# AMP_BB.net
KiCad netlist of a schematic drawn in Altium Designer
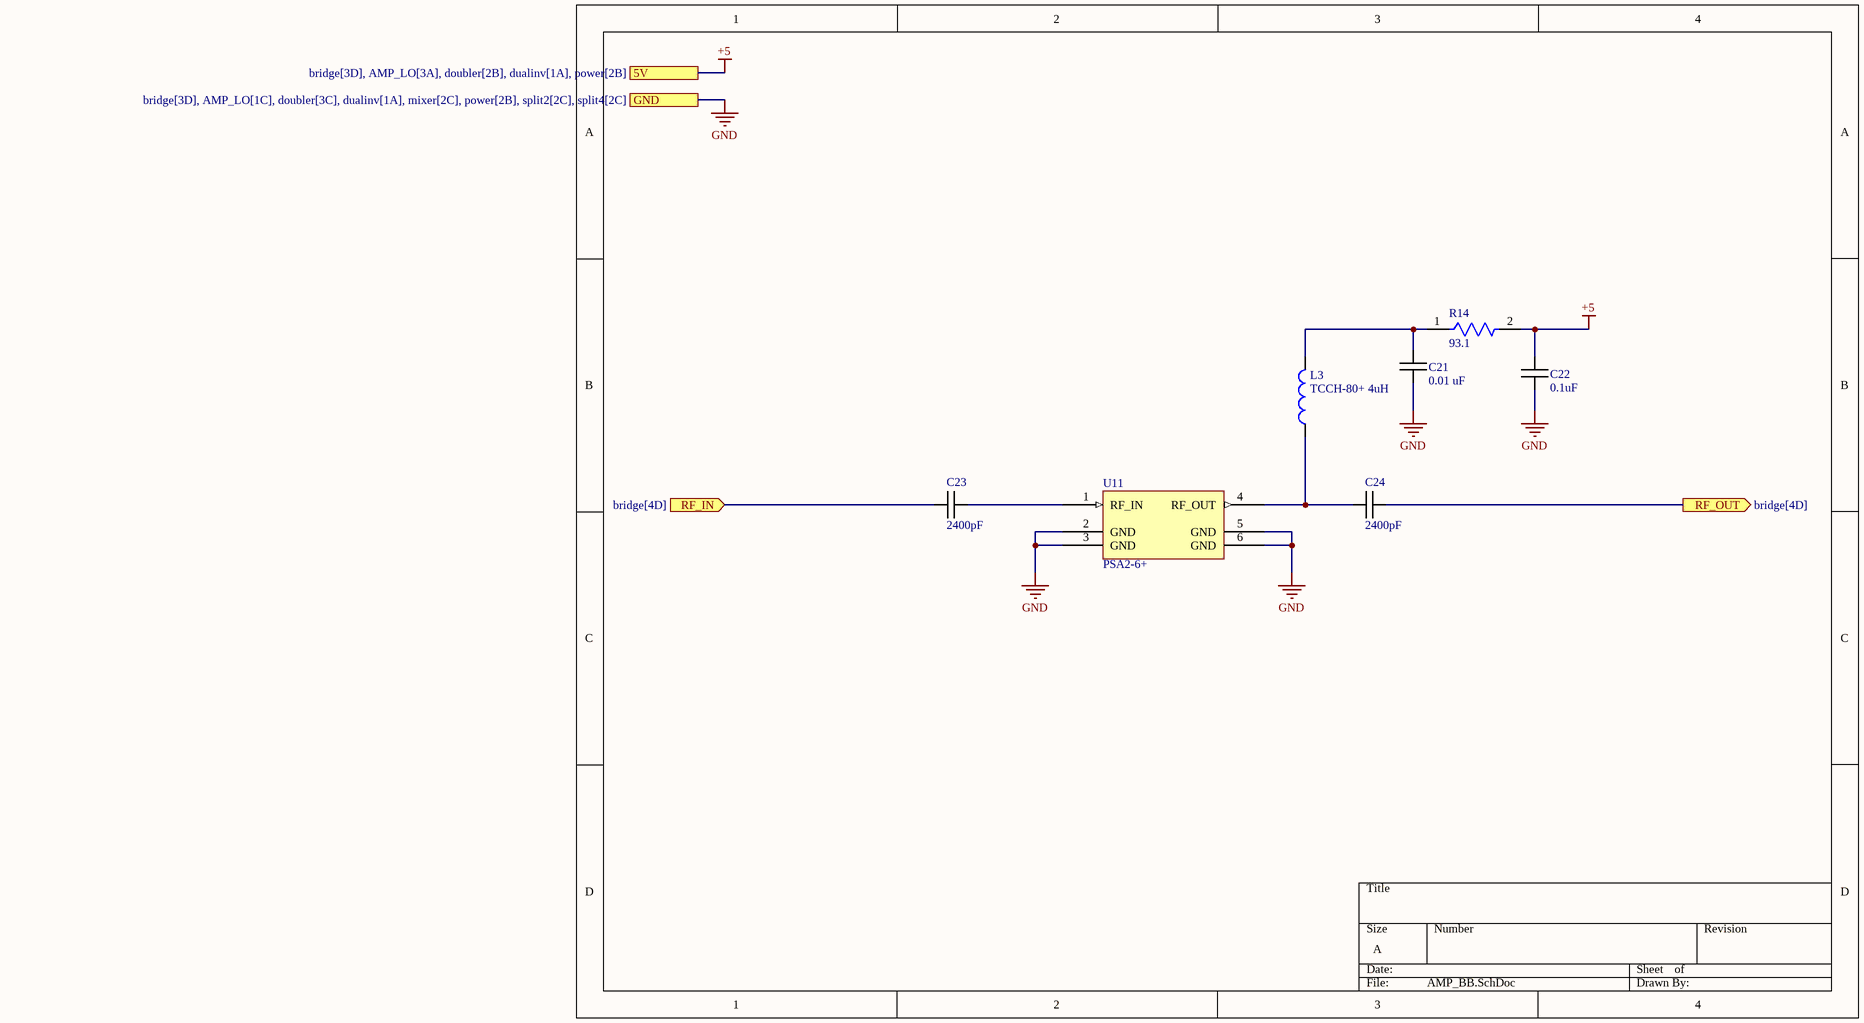
[diagram p0: AMP_BB.SchDoc]

(export (version "E")
  (design (tool "Eeschema 10.0.6"))
  (components
    (comp (ref "C21")
      (value "0.01 uF")
      (footprint "CAP0603_10000pF")
      (description "SMD Capacitor C0G(EIA) with Capacitance: 10000pF Tol. 5%. Rated Voltage: 50Vdc")
      (fields (field (name "PART NUMBER") "GCM1885C1H103JA16D") (field (name "MANUFACTURER") "Murata"))
      (libsource (lib "LCR") (part "GCM1885C1H103JA16D"))
    )
    (comp (ref "C22")
      (value "0.1uF")
      (footprint "CAPC1608X90N")
      (description "SMD Capacitor X8L(MURATA) with Capacitance: 0.10uF Tol. 10%. Rated Voltage: 50Vdc")
      (fields (field (name "MANUFACTURER") "Murata") (field (name "PART NUMBER") "GCM188L81H104KA57D"))
      (libsource (lib "LCR") (part "GCM188L81H104KA57D"))
    )
    (comp (ref "C23")
      (value "2400pF")
      (footprint "CAPC1608X90N")
      (description "CAP CER 2400PF 50V C0G/NP0 0603")
      (fields (field (name "MANUFACTURER") "Murata") (field (name "PART NUMBER") "GCM1885C1H242FA16J"))
      (libsource (lib "LCR") (part "GCM1885C1H242FA16J"))
    )
    (comp (ref "C24")
      (value "2400pF")
      (footprint "CAPC1608X90N")
      (description "CAP CER 2400PF 50V C0G/NP0 0603")
      (fields (field (name "PART NUMBER") "GCM1885C1H242FA16J") (field (name "MANUFACTURER") "Murata"))
      (libsource (lib "LCR") (part "GCM1885C1H242FA16J"))
    )
    (comp (ref "L3")
      (value "TCCH-80+ 4uH")
      (footprint "TCCH-80+")
      (description "SMT RF Choke 50 MHz - 8.2 GHz, 50Ω")
      (fields (field (name "PART NUMBER") "TCCH-80+") (field (name "MANUFACTURER") "Mini-Circuits"))
      (libsource (lib "LCR") (part "TCCH-80+"))
    )
    (comp (ref "R14")
      (value "93.1")
      (footprint "FP-CRCW0805-e3-MFG")
      (description "RES Thick Film, 93.1Ω, 1%, 0.125W, 100ppm/°C, 0805")
      (fields (field (name "TOLERANCE") "1%") (field (name "PART NUMBER") "ERJ-6ENF93R1V"))
      (libsource (lib "FullLib") (part "CMP-2001-04168-2"))
    )
    (comp (ref "U11")
      (value "PSA2-6+")
      (footprint "PSA2-6+ SOT-363")
      (description "SMT MMIC, Linear, Gain Block Amplifier, DC to 7000 MHz, 50Ω, SOT-363 Style Package")
      (fields (field (name "MANUFACTURER") "Mini-Circuits"))
      (libsource (lib "FullyDigital") (part "PSA2-6+"))
    )
  )
  (nets
    (net (code "1") (name "+5") (class "Default")
      (node (ref "C22") (pin "2") (pinfunction "2_2") (pintype "passive"))
      (node (ref "R14") (pin "2") (pinfunction "2_2") (pintype "passive"))
    )
    (net (code "2") (name "/RF_IN") (class "Default")
      (node (ref "C23") (pin "1") (pinfunction "1_1") (pintype "passive"))
    )
    (net (code "3") (name "/RF_OUT") (class "Default")
      (node (ref "C24") (pin "2") (pinfunction "2_2") (pintype "passive"))
    )
    (net (code "4") (name "GND") (class "Default")
      (node (ref "C21") (pin "1") (pinfunction "1_1") (pintype "passive"))
      (node (ref "C22") (pin "1") (pinfunction "1_1") (pintype "passive"))
      (node (ref "U11") (pin "2") (pinfunction "GND_2") (pintype "passive"))
      (node (ref "U11") (pin "3") (pinfunction "GND_3") (pintype "passive"))
      (node (ref "U11") (pin "5") (pinfunction "GND_5") (pintype "passive"))
      (node (ref "U11") (pin "6") (pinfunction "GND_6") (pintype "passive"))
    )
    (net (code "5") (name "Net-(C21-Pad2)") (class "Default")
      (node (ref "C21") (pin "2") (pinfunction "2_2") (pintype "passive"))
      (node (ref "L3") (pin "3") (pinfunction "3_3") (pintype "passive"))
      (node (ref "R14") (pin "1") (pinfunction "1_1") (pintype "passive"))
    )
    (net (code "6") (name "Net-(U11-RF_IN)") (class "Default")
      (node (ref "C23") (pin "2") (pinfunction "2_2") (pintype "passive"))
      (node (ref "U11") (pin "1") (pinfunction "RF_IN_1") (pintype "input"))
    )
    (net (code "7") (name "Net-(U11-RF_OUT)") (class "Default")
      (node (ref "C24") (pin "1") (pinfunction "1_1") (pintype "passive"))
      (node (ref "L3") (pin "1") (pinfunction "1_1") (pintype "passive"))
      (node (ref "U11") (pin "4") (pinfunction "RF_OUT_4") (pintype "output"))
    )
  )
)
